# malp.net
KiCad netlist of a schematic drawn in EAGLE
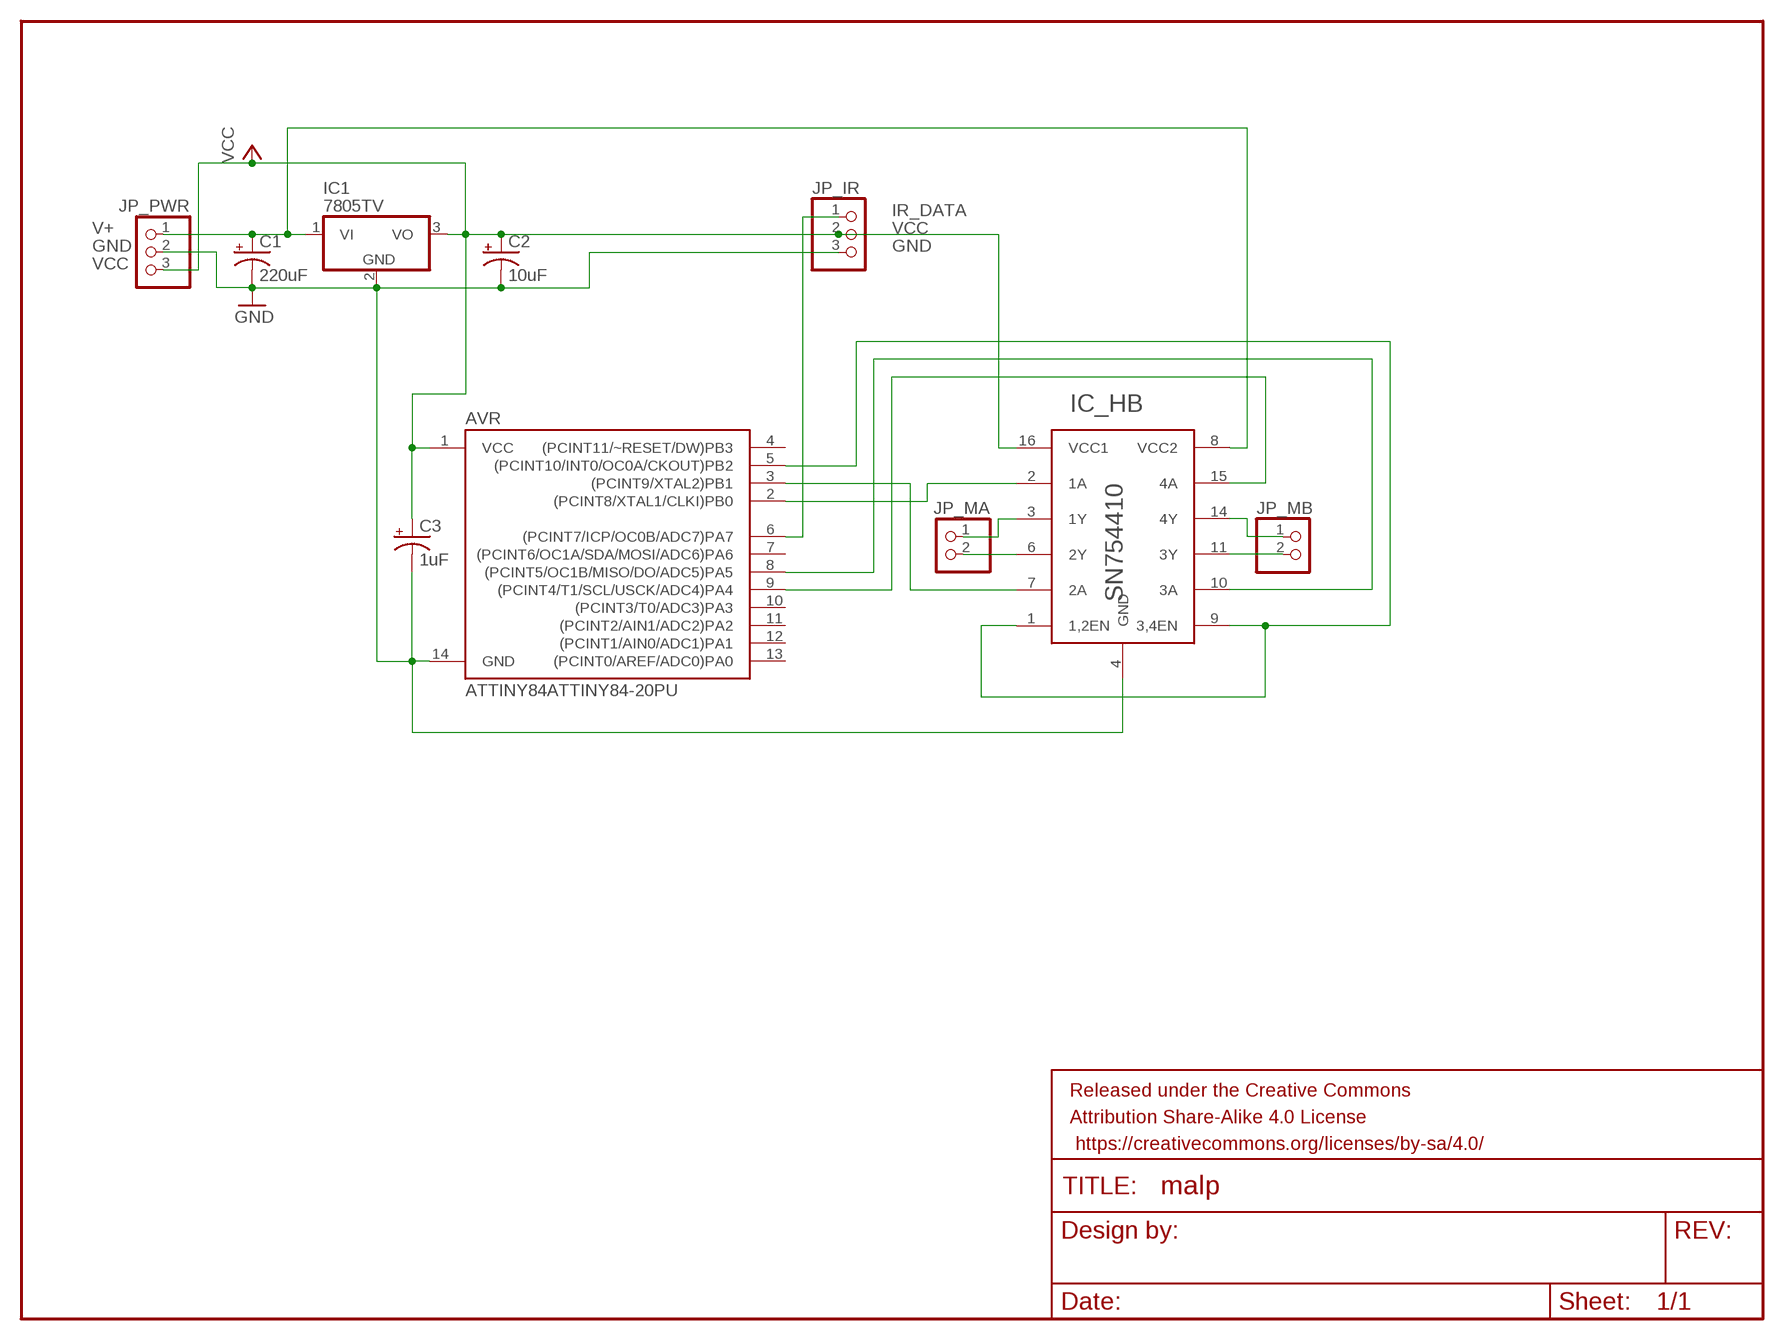
[diagram p0: schematic, sheet 1]

(export (version "E")
  (design (tool "Eeschema 10.0.6"))
  (components
    (comp (ref "AVR")
      (value "ATTINY84ATTINY84-20PU")
      (footprint "eagle-import:DIL14")
      (libsource (lib "eagle-import") (part "ATTINY84ATTINY84-20PU"))
    )
    (comp (ref "C1")
      (value "220uF")
      (footprint "eagle-import:B45181A")
      (libsource (lib "eagle-import") (part "CPOL-USB45181A"))
    )
    (comp (ref "C2")
      (value "10uF")
      (footprint "eagle-import:B45181A")
      (libsource (lib "eagle-import") (part "CPOL-USB45181A"))
    )
    (comp (ref "C3")
      (value "1uF")
      (footprint "eagle-import:B45181A")
      (libsource (lib "eagle-import") (part "CPOL-USB45181A"))
    )
    (comp (ref "FRAME1")
      (value "FRAME-LETTER")
      (footprint "eagle-import:CREATIVE_COMMONS")
      (libsource (lib "eagle-import") (part "FRAME-LETTER"))
    )
    (comp (ref "IC1")
      (value "7805TV")
      (footprint "eagle-import:TO220V")
      (libsource (lib "eagle-import") (part "78TV05"))
    )
    (comp (ref "IC_HB")
      (value "SN754410")
      (footprint "eagle-import:DIL16")
      (libsource (lib "eagle-import") (part "SN754410"))
    )
    (comp (ref "JP_IR")
      (value "PINHD-1X3")
      (footprint "eagle-import:1X03")
      (libsource (lib "eagle-import") (part "PINHD-1X3"))
    )
    (comp (ref "JP_MA")
      (value "PINHD-1X2")
      (footprint "eagle-import:1X02")
      (libsource (lib "eagle-import") (part "PINHD-1X2"))
    )
    (comp (ref "JP_MB")
      (value "PINHD-1X2")
      (footprint "eagle-import:1X02")
      (libsource (lib "eagle-import") (part "PINHD-1X2"))
    )
    (comp (ref "JP_PWR")
      (value "PINHD-1X3")
      (footprint "eagle-import:1X03")
      (libsource (lib "eagle-import") (part "PINHD-1X3"))
    )
  )
  (nets
    (net (code "1") (name "/IR_DATA") (class "Default")
      (node (ref "AVR") (pin "6") (pinfunction "(PCINT7/ICP/OC0B/ADC7)PA7_6") (pintype "bidirectional"))
      (node (ref "JP_IR") (pin "1") (pinfunction "1_1") (pintype "passive"))
    )
    (net (code "2") (name "/V+") (class "Default")
      (node (ref "C1") (pin "+") (pinfunction "+_+") (pintype "passive"))
      (node (ref "IC1") (pin "1") (pinfunction "VI_1") (pintype "input"))
      (node (ref "IC_HB") (pin "8") (pinfunction "VCC2_8") (pintype "power_in"))
      (node (ref "JP_PWR") (pin "1") (pinfunction "1_1") (pintype "passive"))
    )
    (net (code "3") (name "GND") (class "Default")
      (node (ref "AVR") (pin "14") (pinfunction "GND_14") (pintype "bidirectional"))
      (node (ref "C1") (pin "-") (pinfunction "-_-") (pintype "passive"))
      (node (ref "C2") (pin "-") (pinfunction "-_-") (pintype "passive"))
      (node (ref "C3") (pin "-") (pinfunction "-_-") (pintype "passive"))
      (node (ref "IC1") (pin "2") (pinfunction "GND_2") (pintype "passive"))
      (node (ref "IC_HB") (pin "4") (pinfunction "GND_4") (pintype "power_in"))
      (node (ref "JP_IR") (pin "3") (pinfunction "3_3") (pintype "passive"))
      (node (ref "JP_PWR") (pin "2") (pinfunction "2_2") (pintype "passive"))
    )
    (net (code "4") (name "Net-(AVR-(PCINT4{slash}T1{slash}SCL{slash}USCK{slash}ADC4)PA4)") (class "Default")
      (node (ref "AVR") (pin "9") (pinfunction "(PCINT4/T1/SCL/USCK/ADC4)PA4_9") (pintype "bidirectional"))
      (node (ref "IC_HB") (pin "15") (pinfunction "4A_15") (pintype "bidirectional"))
    )
    (net (code "5") (name "Net-(AVR-(PCINT5{slash}OC1B{slash}MISO{slash}DO{slash}ADC5)PA5)") (class "Default")
      (node (ref "AVR") (pin "8") (pinfunction "(PCINT5/OC1B/MISO/DO/ADC5)PA5_8") (pintype "bidirectional"))
      (node (ref "IC_HB") (pin "10") (pinfunction "3A_10") (pintype "bidirectional"))
    )
    (net (code "6") (name "Net-(AVR-(PCINT8{slash}XTAL1{slash}CLKI)PB0)") (class "Default")
      (node (ref "AVR") (pin "2") (pinfunction "(PCINT8/XTAL1/CLKI)PB0_2") (pintype "bidirectional"))
      (node (ref "IC_HB") (pin "2") (pinfunction "1A_2") (pintype "bidirectional"))
    )
    (net (code "7") (name "Net-(AVR-(PCINT9{slash}XTAL2)PB1)") (class "Default")
      (node (ref "AVR") (pin "3") (pinfunction "(PCINT9/XTAL2)PB1_3") (pintype "bidirectional"))
      (node (ref "IC_HB") (pin "7") (pinfunction "2A_7") (pintype "bidirectional"))
    )
    (net (code "8") (name "Net-(AVR-(PCINT10{slash}INT0{slash}OC0A{slash}CKOUT)PB2)") (class "Default")
      (node (ref "AVR") (pin "5") (pinfunction "(PCINT10/INT0/OC0A/CKOUT)PB2_5") (pintype "bidirectional"))
      (node (ref "IC_HB") (pin "1") (pinfunction "1,2EN_1") (pintype "bidirectional"))
      (node (ref "IC_HB") (pin "9") (pinfunction "3,4EN_9") (pintype "bidirectional"))
    )
    (net (code "9") (name "Net-(IC_HBA-1Y)") (class "Default")
      (node (ref "IC_HB") (pin "3") (pinfunction "1Y_3") (pintype "bidirectional"))
      (node (ref "JP_MA") (pin "1") (pinfunction "1_1") (pintype "passive"))
    )
    (net (code "10") (name "Net-(IC_HBA-2Y)") (class "Default")
      (node (ref "IC_HB") (pin "6") (pinfunction "2Y_6") (pintype "bidirectional"))
      (node (ref "JP_MA") (pin "2") (pinfunction "2_2") (pintype "passive"))
    )
    (net (code "11") (name "Net-(IC_HBA-3Y)") (class "Default")
      (node (ref "IC_HB") (pin "11") (pinfunction "3Y_11") (pintype "bidirectional"))
      (node (ref "JP_MB") (pin "2") (pinfunction "2_2") (pintype "passive"))
    )
    (net (code "12") (name "Net-(IC_HBA-4Y)") (class "Default")
      (node (ref "IC_HB") (pin "14") (pinfunction "4Y_14") (pintype "bidirectional"))
      (node (ref "JP_MB") (pin "1") (pinfunction "1_1") (pintype "passive"))
    )
    (net (code "13") (name "VCC") (class "Default")
      (node (ref "AVR") (pin "1") (pinfunction "VCC_1") (pintype "bidirectional"))
      (node (ref "C2") (pin "+") (pinfunction "+_+") (pintype "passive"))
      (node (ref "C3") (pin "+") (pinfunction "+_+") (pintype "passive"))
      (node (ref "IC1") (pin "3") (pinfunction "VO_3") (pintype "passive"))
      (node (ref "IC_HB") (pin "16") (pinfunction "VCC1_16") (pintype "power_in"))
      (node (ref "JP_IR") (pin "2") (pinfunction "2_2") (pintype "passive"))
      (node (ref "JP_PWR") (pin "3") (pinfunction "3_3") (pintype "passive"))
    )
    (net (code "14") (name "unconnected-(AVR-(PCINT0{slash}AREF{slash}ADC0)PA0-Pad13)") (class "Default")
      (node (ref "AVR") (pin "13") (pinfunction "(PCINT0/AREF/ADC0)PA0_13") (pintype "bidirectional"))
    )
    (net (code "15") (name "unconnected-(AVR-(PCINT1{slash}AIN0{slash}ADC1)PA1-Pad12)") (class "Default")
      (node (ref "AVR") (pin "12") (pinfunction "(PCINT1/AIN0/ADC1)PA1_12") (pintype "bidirectional"))
    )
    (net (code "16") (name "unconnected-(AVR-(PCINT2{slash}AIN1{slash}ADC2)PA2-Pad11)") (class "Default")
      (node (ref "AVR") (pin "11") (pinfunction "(PCINT2/AIN1/ADC2)PA2_11") (pintype "bidirectional"))
    )
    (net (code "17") (name "unconnected-(AVR-(PCINT3{slash}T0{slash}ADC3)PA3-Pad10)") (class "Default")
      (node (ref "AVR") (pin "10") (pinfunction "(PCINT3/T0/ADC3)PA3_10") (pintype "bidirectional"))
    )
    (net (code "18") (name "unconnected-(AVR-(PCINT6{slash}OC1A{slash}SDA{slash}MOSI{slash}ADC6)PA6-Pad7)") (class "Default")
      (node (ref "AVR") (pin "7") (pinfunction "(PCINT6/OC1A/SDA/MOSI/ADC6)PA6_7") (pintype "bidirectional"))
    )
    (net (code "19") (name "unconnected-(AVR-(PCINT11{slash}~{RESET{slash}DW})PB3-Pad4)") (class "Default")
      (node (ref "AVR") (pin "4") (pinfunction "(PCINT11/~{RESET/DW})PB3_4") (pintype "bidirectional"))
    )
  )
)
